# Main_v1.net
KiCad netlist of a schematic drawn in EAGLE
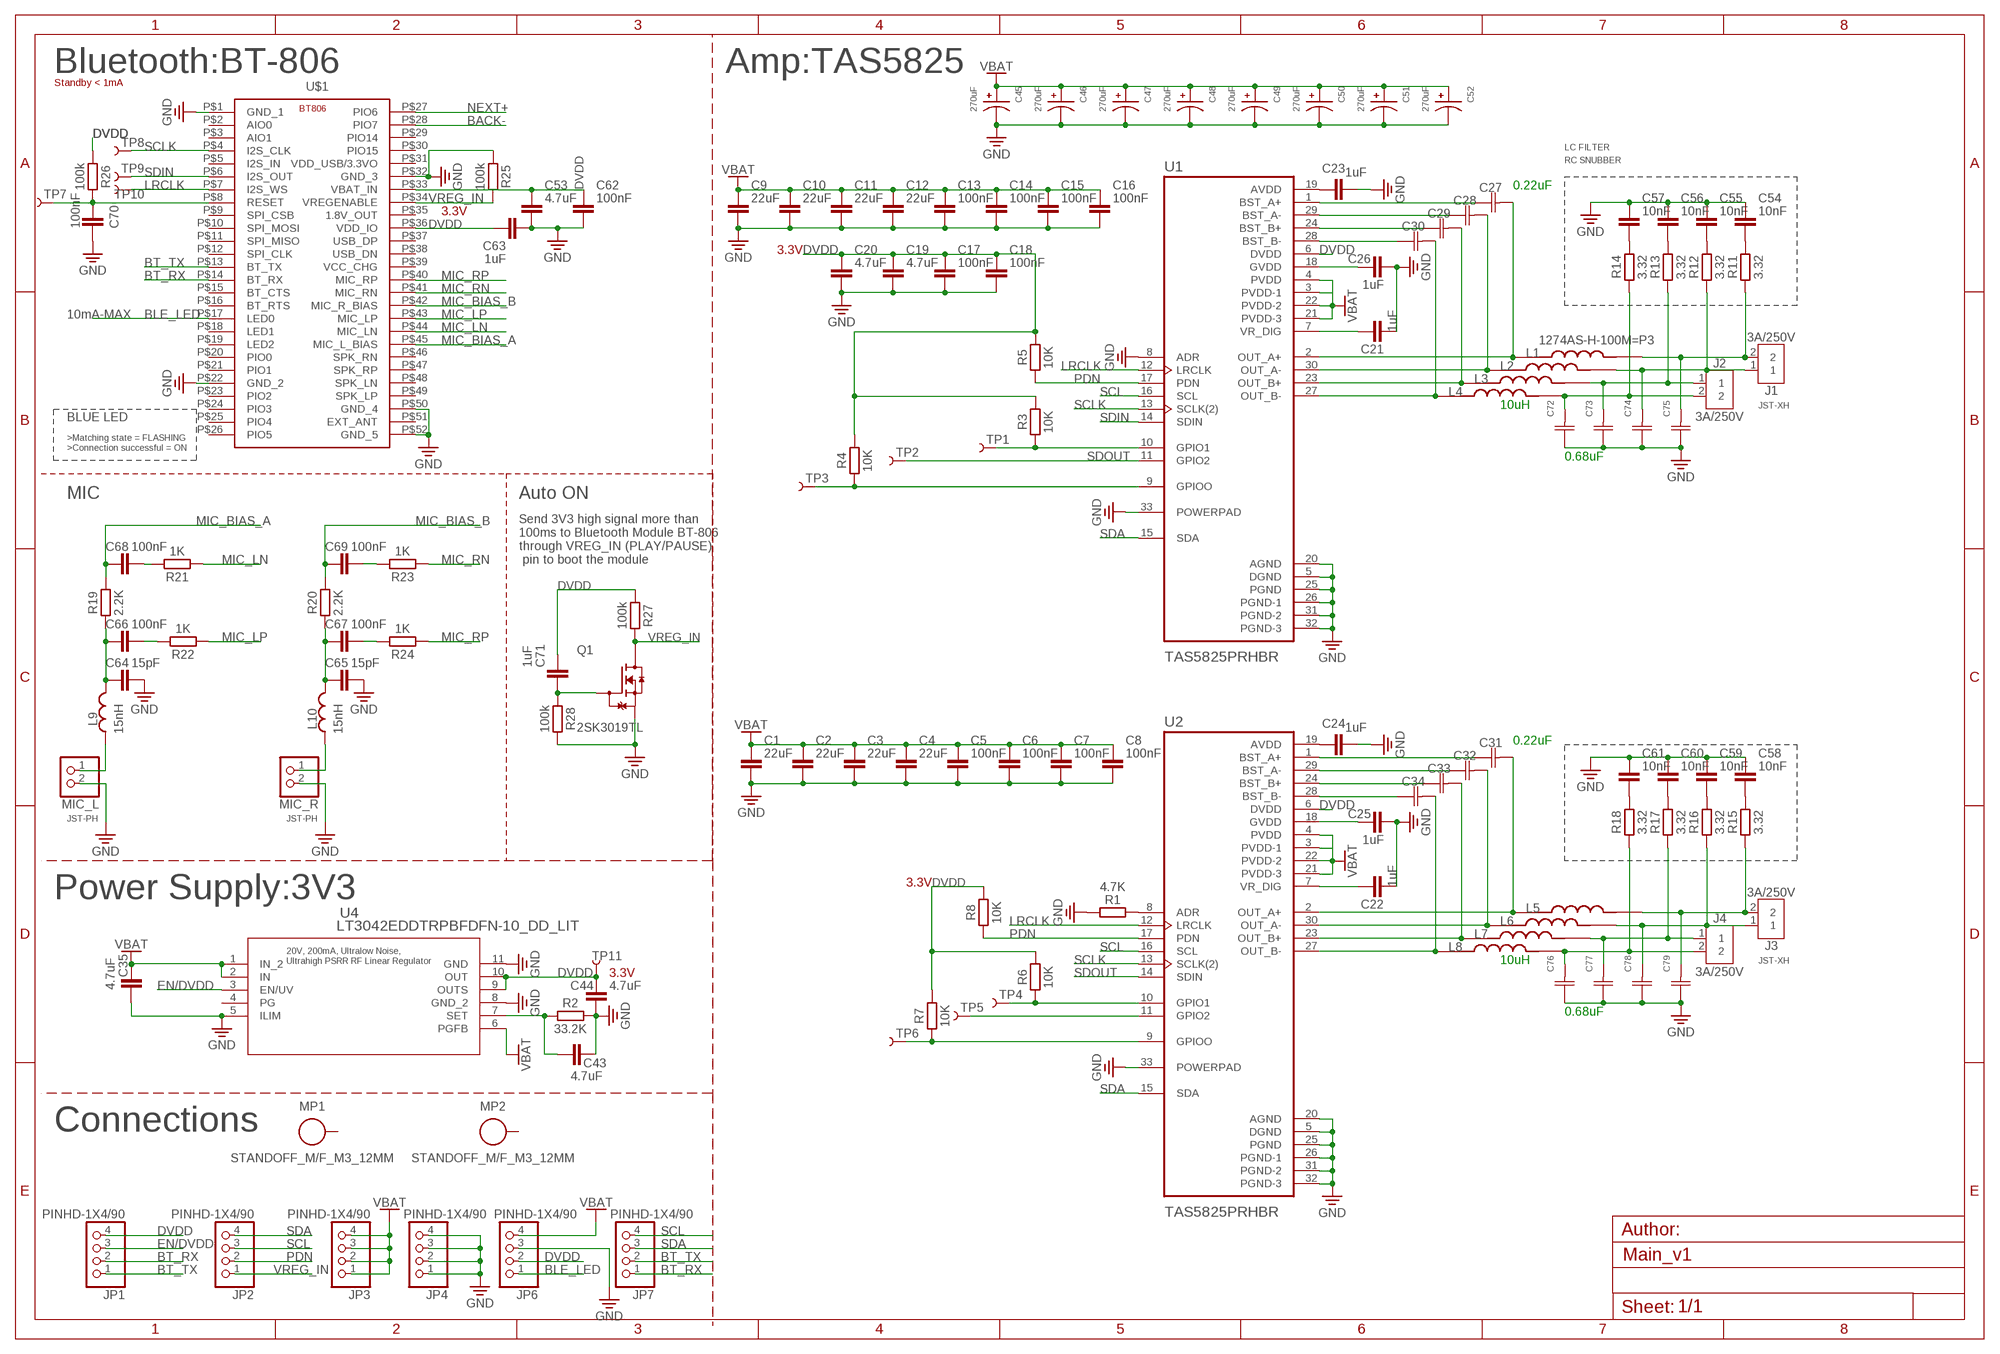
[diagram p0: schematic, sheet 1]

(export (version "E")
  (design (tool "Eeschema 10.0.6"))
  (components
    (comp (ref "C1")
      (value "22uF")
      (footprint "eagle-import:CAPC2012X110")
      (libsource (lib "eagle-import") (part "CCHIP-0805(2012-METRIC)_"))
    )
    (comp (ref "C2")
      (value "22uF")
      (footprint "eagle-import:CAPC2012X110")
      (libsource (lib "eagle-import") (part "CCHIP-0805(2012-METRIC)_"))
    )
    (comp (ref "C3")
      (value "22uF")
      (footprint "eagle-import:CAPC2012X110")
      (libsource (lib "eagle-import") (part "CCHIP-0805(2012-METRIC)_"))
    )
    (comp (ref "C4")
      (value "22uF")
      (footprint "eagle-import:CAPC2012X110")
      (libsource (lib "eagle-import") (part "CCHIP-0805(2012-METRIC)_"))
    )
    (comp (ref "C5")
      (value "100nF")
      (footprint "eagle-import:CAPC2012X110")
      (libsource (lib "eagle-import") (part "CCHIP-0805(2012-METRIC)_"))
    )
    (comp (ref "C6")
      (value "100nF")
      (footprint "eagle-import:CAPC2012X110")
      (libsource (lib "eagle-import") (part "CCHIP-0805(2012-METRIC)_"))
    )
    (comp (ref "C7")
      (value "100nF")
      (footprint "eagle-import:CAPC2012X110")
      (libsource (lib "eagle-import") (part "CCHIP-0805(2012-METRIC)_"))
    )
    (comp (ref "C8")
      (value "100nF")
      (footprint "eagle-import:CAPC2012X110")
      (libsource (lib "eagle-import") (part "CCHIP-0805(2012-METRIC)_"))
    )
    (comp (ref "C9")
      (value "22uF")
      (footprint "eagle-import:CAPC2012X110")
      (libsource (lib "eagle-import") (part "CCHIP-0805(2012-METRIC)_"))
    )
    (comp (ref "C10")
      (value "22uF")
      (footprint "eagle-import:CAPC2012X110")
      (libsource (lib "eagle-import") (part "CCHIP-0805(2012-METRIC)_"))
    )
    (comp (ref "C11")
      (value "22uF")
      (footprint "eagle-import:CAPC2012X110")
      (libsource (lib "eagle-import") (part "CCHIP-0805(2012-METRIC)_"))
    )
    (comp (ref "C12")
      (value "22uF")
      (footprint "eagle-import:CAPC2012X110")
      (libsource (lib "eagle-import") (part "CCHIP-0805(2012-METRIC)_"))
    )
    (comp (ref "C13")
      (value "100nF")
      (footprint "eagle-import:CAPC2012X110")
      (libsource (lib "eagle-import") (part "CCHIP-0805(2012-METRIC)_"))
    )
    (comp (ref "C14")
      (value "100nF")
      (footprint "eagle-import:CAPC2012X110")
      (libsource (lib "eagle-import") (part "CCHIP-0805(2012-METRIC)_"))
    )
    (comp (ref "C15")
      (value "100nF")
      (footprint "eagle-import:CAPC2012X110")
      (libsource (lib "eagle-import") (part "CCHIP-0805(2012-METRIC)_"))
    )
    (comp (ref "C16")
      (value "100nF")
      (footprint "eagle-import:CAPC2012X110")
      (libsource (lib "eagle-import") (part "CCHIP-0805(2012-METRIC)_"))
    )
    (comp (ref "C17")
      (value "100nF")
      (footprint "eagle-import:CAPC2012X110")
      (libsource (lib "eagle-import") (part "CCHIP-0805(2012-METRIC)_"))
    )
    (comp (ref "C18")
      (value "100nF")
      (footprint "eagle-import:CAPC2012X110")
      (libsource (lib "eagle-import") (part "CCHIP-0805(2012-METRIC)_"))
    )
    (comp (ref "C19")
      (value "4.7uF")
      (footprint "eagle-import:CAPC3216X135")
      (libsource (lib "eagle-import") (part "CCHIP-1206(3216-METRIC)_"))
    )
    (comp (ref "C20")
      (value "4.7uF")
      (footprint "eagle-import:CAPC3216X135")
      (libsource (lib "eagle-import") (part "CCHIP-1206(3216-METRIC)_"))
    )
    (comp (ref "C21")
      (value "1uF")
      (footprint "eagle-import:CAPC2012X110")
      (libsource (lib "eagle-import") (part "CCHIP-0805(2012-METRIC)_"))
    )
    (comp (ref "C22")
      (value "1uF")
      (footprint "eagle-import:CAPC2012X110")
      (libsource (lib "eagle-import") (part "CCHIP-0805(2012-METRIC)_"))
    )
    (comp (ref "C23")
      (value "1uF")
      (footprint "eagle-import:CAPC2012X110")
      (libsource (lib "eagle-import") (part "CCHIP-0805(2012-METRIC)_"))
    )
    (comp (ref "C24")
      (value "1uF")
      (footprint "eagle-import:CAPC2012X110")
      (libsource (lib "eagle-import") (part "CCHIP-0805(2012-METRIC)_"))
    )
    (comp (ref "C25")
      (value "1uF")
      (footprint "eagle-import:CAPC2012X110")
      (libsource (lib "eagle-import") (part "CCHIP-0805(2012-METRIC)_"))
    )
    (comp (ref "C26")
      (value "1uF")
      (footprint "eagle-import:CAPC2012X110")
      (libsource (lib "eagle-import") (part "CCHIP-0805(2012-METRIC)_"))
    )
    (comp (ref "C27")
      (value "0.22uF")
      (footprint "eagle-import:CAPM7.2X7.2_5_1_VIS")
      (fields
        (field (name "MANUFACTURER_PART_NUMBER") "PHE426HJ6220JR05")
        (field (name "COPYRIGHT") "Copyright (C) 2021 Ultra Librarian. All rights reserved.")
      )
      (libsource (lib "eagle-import") (part "PHE426HJ6220JR05CAPM7.2X7.2_5_1_VIS"))
    )
    (comp (ref "C28")
      (value "0.22uF")
      (footprint "eagle-import:CAPM7.2X7.2_5_1_VIS")
      (fields
        (field (name "MANUFACTURER_PART_NUMBER") "PHE426HJ6220JR05")
        (field (name "COPYRIGHT") "Copyright (C) 2021 Ultra Librarian. All rights reserved.")
      )
      (libsource (lib "eagle-import") (part "PHE426HJ6220JR05CAPM7.2X7.2_5_1_VIS"))
    )
    (comp (ref "C29")
      (value "0.22uF")
      (footprint "eagle-import:CAPM7.2X7.2_5_1_VIS")
      (fields
        (field (name "MANUFACTURER_PART_NUMBER") "PHE426HJ6220JR05")
        (field (name "COPYRIGHT") "Copyright (C) 2021 Ultra Librarian. All rights reserved.")
      )
      (libsource (lib "eagle-import") (part "PHE426HJ6220JR05CAPM7.2X7.2_5_1_VIS"))
    )
    (comp (ref "C30")
      (value "0.22uF")
      (footprint "eagle-import:CAPM7.2X7.2_5_1_VIS")
      (fields
        (field (name "MANUFACTURER_PART_NUMBER") "PHE426HJ6220JR05")
        (field (name "COPYRIGHT") "Copyright (C) 2021 Ultra Librarian. All rights reserved.")
      )
      (libsource (lib "eagle-import") (part "PHE426HJ6220JR05CAPM7.2X7.2_5_1_VIS"))
    )
    (comp (ref "C31")
      (value "0.22uF")
      (footprint "eagle-import:CAPM7.2X7.2_5_1_VIS")
      (fields
        (field (name "MANUFACTURER_PART_NUMBER") "PHE426HJ6220JR05")
        (field (name "COPYRIGHT") "Copyright (C) 2021 Ultra Librarian. All rights reserved.")
      )
      (libsource (lib "eagle-import") (part "PHE426HJ6220JR05CAPM7.2X7.2_5_1_VIS"))
    )
    (comp (ref "C32")
      (value "0.22uF")
      (footprint "eagle-import:CAPM7.2X7.2_5_1_VIS")
      (fields
        (field (name "MANUFACTURER_PART_NUMBER") "PHE426HJ6220JR05")
        (field (name "COPYRIGHT") "Copyright (C) 2021 Ultra Librarian. All rights reserved.")
      )
      (libsource (lib "eagle-import") (part "PHE426HJ6220JR05CAPM7.2X7.2_5_1_VIS"))
    )
    (comp (ref "C33")
      (value "0.22uF")
      (footprint "eagle-import:CAPM7.2X7.2_5_1_VIS")
      (fields
        (field (name "MANUFACTURER_PART_NUMBER") "PHE426HJ6220JR05")
        (field (name "COPYRIGHT") "Copyright (C) 2021 Ultra Librarian. All rights reserved.")
      )
      (libsource (lib "eagle-import") (part "PHE426HJ6220JR05CAPM7.2X7.2_5_1_VIS"))
    )
    (comp (ref "C34")
      (value "0.22uF")
      (footprint "eagle-import:CAPM7.2X7.2_5_1_VIS")
      (fields
        (field (name "MANUFACTURER_PART_NUMBER") "PHE426HJ6220JR05")
        (field (name "COPYRIGHT") "Copyright (C) 2021 Ultra Librarian. All rights reserved.")
      )
      (libsource (lib "eagle-import") (part "PHE426HJ6220JR05CAPM7.2X7.2_5_1_VIS"))
    )
    (comp (ref "C35")
      (value "4.7uF")
      (footprint "eagle-import:CAPC2012X110")
      (libsource (lib "eagle-import") (part "CCHIP-0805(2012-METRIC)_"))
    )
    (comp (ref "C43")
      (value "4.7uF")
      (footprint "eagle-import:CAPC2012X110")
      (libsource (lib "eagle-import") (part "CCHIP-0805(2012-METRIC)_"))
    )
    (comp (ref "C44")
      (value "4.7uF")
      (footprint "eagle-import:CAPC2012X110")
      (libsource (lib "eagle-import") (part "CCHIP-0805(2012-METRIC)_"))
    )
    (comp (ref "C45")
      (value "270uF")
      (footprint "eagle-import:CAP_16SVPG270M")
      (fields (field (name "MANUFACTURER") "Panasonic"))
      (libsource (lib "eagle-import") (part "16SVPG270M"))
    )
    (comp (ref "C46")
      (value "270uF")
      (footprint "eagle-import:CAP_16SVPG270M")
      (fields (field (name "MANUFACTURER") "Panasonic"))
      (libsource (lib "eagle-import") (part "16SVPG270M"))
    )
    (comp (ref "C47")
      (value "270uF")
      (footprint "eagle-import:CAP_16SVPG270M")
      (fields (field (name "MANUFACTURER") "Panasonic"))
      (libsource (lib "eagle-import") (part "16SVPG270M"))
    )
    (comp (ref "C48")
      (value "270uF")
      (footprint "eagle-import:CAP_16SVPG270M")
      (fields (field (name "MANUFACTURER") "Panasonic"))
      (libsource (lib "eagle-import") (part "16SVPG270M"))
    )
    (comp (ref "C49")
      (value "270uF")
      (footprint "eagle-import:CAP_16SVPG270M")
      (fields (field (name "MANUFACTURER") "Panasonic"))
      (libsource (lib "eagle-import") (part "16SVPG270M"))
    )
    (comp (ref "C50")
      (value "270uF")
      (footprint "eagle-import:CAP_16SVPG270M")
      (fields (field (name "MANUFACTURER") "Panasonic"))
      (libsource (lib "eagle-import") (part "16SVPG270M"))
    )
    (comp (ref "C51")
      (value "270uF")
      (footprint "eagle-import:CAP_16SVPG270M")
      (fields (field (name "MANUFACTURER") "Panasonic"))
      (libsource (lib "eagle-import") (part "16SVPG270M"))
    )
    (comp (ref "C52")
      (value "270uF")
      (footprint "eagle-import:CAP_16SVPG270M")
      (fields (field (name "MANUFACTURER") "Panasonic"))
      (libsource (lib "eagle-import") (part "16SVPG270M"))
    )
    (comp (ref "C53")
      (value "4.7uF")
      (footprint "eagle-import:CAPC2012X110")
      (libsource (lib "eagle-import") (part "CCHIP-0805(2012-METRIC)_"))
    )
    (comp (ref "C54")
      (value "10nF")
      (footprint "eagle-import:CAPC2012X110")
      (libsource (lib "eagle-import") (part "CCHIP-0805(2012-METRIC)_"))
    )
    (comp (ref "C55")
      (value "10nF")
      (footprint "eagle-import:CAPC2012X110")
      (libsource (lib "eagle-import") (part "CCHIP-0805(2012-METRIC)_"))
    )
    (comp (ref "C56")
      (value "10nF")
      (footprint "eagle-import:CAPC2012X110")
      (libsource (lib "eagle-import") (part "CCHIP-0805(2012-METRIC)_"))
    )
    (comp (ref "C57")
      (value "10nF")
      (footprint "eagle-import:CAPC2012X110")
      (libsource (lib "eagle-import") (part "CCHIP-0805(2012-METRIC)_"))
    )
    (comp (ref "C58")
      (value "10nF")
      (footprint "eagle-import:CAPC2012X110")
      (libsource (lib "eagle-import") (part "CCHIP-0805(2012-METRIC)_"))
    )
    (comp (ref "C59")
      (value "10nF")
      (footprint "eagle-import:CAPC2012X110")
      (libsource (lib "eagle-import") (part "CCHIP-0805(2012-METRIC)_"))
    )
    (comp (ref "C60")
      (value "10nF")
      (footprint "eagle-import:CAPC2012X110")
      (libsource (lib "eagle-import") (part "CCHIP-0805(2012-METRIC)_"))
    )
    (comp (ref "C61")
      (value "10nF")
      (footprint "eagle-import:CAPC2012X110")
      (libsource (lib "eagle-import") (part "CCHIP-0805(2012-METRIC)_"))
    )
    (comp (ref "C62")
      (value "100nF")
      (footprint "eagle-import:CAPC2012X110")
      (libsource (lib "eagle-import") (part "CCHIP-0805(2012-METRIC)_"))
    )
    (comp (ref "C63")
      (value "1uF")
      (footprint "eagle-import:CAPC2012X110")
      (libsource (lib "eagle-import") (part "CCHIP-0805(2012-METRIC)_"))
    )
    (comp (ref "C64")
      (value "15pF")
      (footprint "eagle-import:CAPC1005X60")
      (libsource (lib "eagle-import") (part "CCHIP-0402(1005-METRIC)_"))
    )
    (comp (ref "C65")
      (value "15pF")
      (footprint "eagle-import:CAPC1005X60")
      (libsource (lib "eagle-import") (part "CCHIP-0402(1005-METRIC)_"))
    )
    (comp (ref "C66")
      (value "100nF")
      (footprint "eagle-import:CAPC1005X60")
      (libsource (lib "eagle-import") (part "CCHIP-0402(1005-METRIC)_"))
    )
    (comp (ref "C67")
      (value "100nF")
      (footprint "eagle-import:CAPC1005X60")
      (libsource (lib "eagle-import") (part "CCHIP-0402(1005-METRIC)_"))
    )
    (comp (ref "C68")
      (value "100nF")
      (footprint "eagle-import:CAPC1005X60")
      (libsource (lib "eagle-import") (part "CCHIP-0402(1005-METRIC)_"))
    )
    (comp (ref "C69")
      (value "100nF")
      (footprint "eagle-import:CAPC1005X60")
      (libsource (lib "eagle-import") (part "CCHIP-0402(1005-METRIC)_"))
    )
    (comp (ref "C70")
      (value "100nF")
      (footprint "eagle-import:CAPC1005X60")
      (libsource (lib "eagle-import") (part "CCHIP-0402(1005-METRIC)_"))
    )
    (comp (ref "C71")
      (value "1uF")
      (footprint "eagle-import:CAPC2012X110")
      (libsource (lib "eagle-import") (part "CCHIP-0805(2012-METRIC)_"))
    )
    (comp (ref "C72")
      (value "MMK5684J63J03L16.5TR18CAPM7.2X4.5_5_VIS")
      (footprint "eagle-import:CAPM7.2X4.5_5_VIS")
      (fields
        (field (name "MANUFACTURER_PART_NUMBER") "MMK5684J63J03L16.5TR18")
        (field (name "COPYRIGHT") "Copyright (C) 2022 Ultra Librarian. All rights reserved.")
      )
      (libsource (lib "eagle-import") (part "MMK5684J63J03L16.5TR18CAPM7.2X4.5_5_VIS"))
    )
    (comp (ref "C73")
      (value "MMK5684J63J03L16.5TR18CAPM7.2X4.5_5_VIS")
      (footprint "eagle-import:CAPM7.2X4.5_5_VIS")
      (fields
        (field (name "MANUFACTURER_PART_NUMBER") "MMK5684J63J03L16.5TR18")
        (field (name "COPYRIGHT") "Copyright (C) 2022 Ultra Librarian. All rights reserved.")
      )
      (libsource (lib "eagle-import") (part "MMK5684J63J03L16.5TR18CAPM7.2X4.5_5_VIS"))
    )
    (comp (ref "C74")
      (value "MMK5684J63J03L16.5TR18CAPM7.2X4.5_5_VIS")
      (footprint "eagle-import:CAPM7.2X4.5_5_VIS")
      (fields
        (field (name "MANUFACTURER_PART_NUMBER") "MMK5684J63J03L16.5TR18")
        (field (name "COPYRIGHT") "Copyright (C) 2022 Ultra Librarian. All rights reserved.")
      )
      (libsource (lib "eagle-import") (part "MMK5684J63J03L16.5TR18CAPM7.2X4.5_5_VIS"))
    )
    (comp (ref "C75")
      (value "MMK5684J63J03L16.5TR18CAPM7.2X4.5_5_VIS")
      (footprint "eagle-import:CAPM7.2X4.5_5_VIS")
      (fields
        (field (name "MANUFACTURER_PART_NUMBER") "MMK5684J63J03L16.5TR18")
        (field (name "COPYRIGHT") "Copyright (C) 2022 Ultra Librarian. All rights reserved.")
      )
      (libsource (lib "eagle-import") (part "MMK5684J63J03L16.5TR18CAPM7.2X4.5_5_VIS"))
    )
    (comp (ref "C76")
      (value "MMK5684J63J03L16.5TR18CAPM7.2X4.5_5_VIS")
      (footprint "eagle-import:CAPM7.2X4.5_5_VIS")
      (fields
        (field (name "MANUFACTURER_PART_NUMBER") "MMK5684J63J03L16.5TR18")
        (field (name "COPYRIGHT") "Copyright (C) 2022 Ultra Librarian. All rights reserved.")
      )
      (libsource (lib "eagle-import") (part "MMK5684J63J03L16.5TR18CAPM7.2X4.5_5_VIS"))
    )
    (comp (ref "C77")
      (value "MMK5684J63J03L16.5TR18CAPM7.2X4.5_5_VIS")
      (footprint "eagle-import:CAPM7.2X4.5_5_VIS")
      (fields
        (field (name "MANUFACTURER_PART_NUMBER") "MMK5684J63J03L16.5TR18")
        (field (name "COPYRIGHT") "Copyright (C) 2022 Ultra Librarian. All rights reserved.")
      )
      (libsource (lib "eagle-import") (part "MMK5684J63J03L16.5TR18CAPM7.2X4.5_5_VIS"))
    )
    (comp (ref "C78")
      (value "MMK5684J63J03L16.5TR18CAPM7.2X4.5_5_VIS")
      (footprint "eagle-import:CAPM7.2X4.5_5_VIS")
      (fields
        (field (name "MANUFACTURER_PART_NUMBER") "MMK5684J63J03L16.5TR18")
        (field (name "COPYRIGHT") "Copyright (C) 2022 Ultra Librarian. All rights reserved.")
      )
      (libsource (lib "eagle-import") (part "MMK5684J63J03L16.5TR18CAPM7.2X4.5_5_VIS"))
    )
    (comp (ref "C79")
      (value "MMK5684J63J03L16.5TR18CAPM7.2X4.5_5_VIS")
      (footprint "eagle-import:CAPM7.2X4.5_5_VIS")
      (fields
        (field (name "MANUFACTURER_PART_NUMBER") "MMK5684J63J03L16.5TR18")
        (field (name "COPYRIGHT") "Copyright (C) 2022 Ultra Librarian. All rights reserved.")
      )
      (libsource (lib "eagle-import") (part "MMK5684J63J03L16.5TR18CAPM7.2X4.5_5_VIS"))
    )
    (comp (ref "J1")
      (value "3A/250V")
      (footprint "eagle-import:B2B-XH-A")
      (fields (field (name "MANUFACTURER") "JST (XH CONNECTOR)") (field (name "MPN") "B2B-XH-A"))
      (libsource (lib "eagle-import") (part "B2B-XH-A"))
    )
    (comp (ref "J2")
      (value "3A/250V")
      (footprint "eagle-import:B2B-XH-A")
      (fields (field (name "MANUFACTURER") "JST (XH CONNECTOR)") (field (name "MPN") "B2B-XH-A"))
      (libsource (lib "eagle-import") (part "B2B-XH-A"))
    )
    (comp (ref "J3")
      (value "3A/250V")
      (footprint "eagle-import:B2B-XH-A")
      (fields (field (name "MANUFACTURER") "JST (XH CONNECTOR)") (field (name "MPN") "B2B-XH-A"))
      (libsource (lib "eagle-import") (part "B2B-XH-A"))
    )
    (comp (ref "J4")
      (value "3A/250V")
      (footprint "eagle-import:B2B-XH-A")
      (fields (field (name "MANUFACTURER") "JST (XH CONNECTOR)") (field (name "MPN") "B2B-XH-A"))
      (libsource (lib "eagle-import") (part "B2B-XH-A"))
    )
    (comp (ref "JP1")
      (value "PINHD-1X4/90")
      (footprint "eagle-import:1X04_90")
      (libsource (lib "eagle-import") (part "PINHD-1X4/90"))
    )
    (comp (ref "JP2")
      (value "PINHD-1X4/90")
      (footprint "eagle-import:1X04_90")
      (libsource (lib "eagle-import") (part "PINHD-1X4/90"))
    )
    (comp (ref "JP3")
      (value "PINHD-1X4/90")
      (footprint "eagle-import:1X04_90")
      (libsource (lib "eagle-import") (part "PINHD-1X4/90"))
    )
    (comp (ref "JP4")
      (value "PINHD-1X4/90")
      (footprint "eagle-import:1X04_90")
      (libsource (lib "eagle-import") (part "PINHD-1X4/90"))
    )
    (comp (ref "JP6")
      (value "PINHD-1X4/90")
      (footprint "eagle-import:1X04_90")
      (libsource (lib "eagle-import") (part "PINHD-1X4/90"))
    )
    (comp (ref "JP7")
      (value "PINHD-1X4/90")
      (footprint "eagle-import:1X04_90")
      (libsource (lib "eagle-import") (part "PINHD-1X4/90"))
    )
    (comp (ref "L1")
      (value "1274AS-H-100M=P3")
      (footprint "eagle-import:IND_1274AS-H-100M=P3")
      (fields (field (name "MANUFACTURER") "Murata"))
      (libsource (lib "eagle-import") (part "1274AS-H-100M=P3"))
    )
    (comp (ref "L2")
      (value "1274AS-H-100M=P3")
      (footprint "eagle-import:IND_1274AS-H-100M=P3")
      (fields (field (name "MANUFACTURER") "Murata"))
      (libsource (lib "eagle-import") (part "1274AS-H-100M=P3"))
    )
    (comp (ref "L3")
      (value "1274AS-H-100M=P3")
      (footprint "eagle-import:IND_1274AS-H-100M=P3")
      (fields (field (name "MANUFACTURER") "Murata"))
      (libsource (lib "eagle-import") (part "1274AS-H-100M=P3"))
    )
    (comp (ref "L4")
      (value "1274AS-H-100M=P3")
      (footprint "eagle-import:IND_1274AS-H-100M=P3")
      (fields (field (name "MANUFACTURER") "Murata"))
      (libsource (lib "eagle-import") (part "1274AS-H-100M=P3"))
    )
    (comp (ref "L5")
      (value "1274AS-H-100M=P3")
      (footprint "eagle-import:IND_1274AS-H-100M=P3")
      (fields (field (name "MANUFACTURER") "Murata"))
      (libsource (lib "eagle-import") (part "1274AS-H-100M=P3"))
    )
    (comp (ref "L6")
      (value "1274AS-H-100M=P3")
      (footprint "eagle-import:IND_1274AS-H-100M=P3")
      (fields (field (name "MANUFACTURER") "Murata"))
      (libsource (lib "eagle-import") (part "1274AS-H-100M=P3"))
    )
    (comp (ref "L7")
      (value "1274AS-H-100M=P3")
      (footprint "eagle-import:IND_1274AS-H-100M=P3")
      (fields (field (name "MANUFACTURER") "Murata"))
      (libsource (lib "eagle-import") (part "1274AS-H-100M=P3"))
    )
    (comp (ref "L8")
      (value "1274AS-H-100M=P3")
      (footprint "eagle-import:IND_1274AS-H-100M=P3")
      (fields (field (name "MANUFACTURER") "Murata"))
      (libsource (lib "eagle-import") (part "1274AS-H-100M=P3"))
    )
    (comp (ref "L9")
      (value "15nH")
      (footprint "eagle-import:INDC1006X60N")
      (libsource (lib "eagle-import") (part "LCHIP-0402(1006-METRIC)_"))
    )
    (comp (ref "L10")
      (value "15nH")
      (footprint "eagle-import:INDC1006X60N")
      (libsource (lib "eagle-import") (part "LCHIP-0402(1006-METRIC)_"))
    )
    (comp (ref "MIC_L")
      (value "JST_2PIN-THM")
      (footprint "eagle-import:JST-PH-2-THM")
      (libsource (lib "eagle-import") (part "JST_2PIN-THM"))
    )
    (comp (ref "MIC_R")
      (value "JST_2PIN-THM")
      (footprint "eagle-import:JST-PH-2-THM")
      (libsource (lib "eagle-import") (part "JST_2PIN-THM"))
    )
    (comp (ref "MP1")
      (value "STANDOFF_M/F_M3_12MM")
      (footprint "eagle-import:STANDOFF_HEX_MALE-FEMALE_550X1200_M3X0.5_MTGP850H320")
      (libsource (lib "eagle-import") (part "STANDOFF_M/FM3_12MM_"))
    )
    (comp (ref "MP2")
      (value "STANDOFF_M/F_M3_12MM")
      (footprint "eagle-import:STANDOFF_HEX_MALE-FEMALE_550X1200_M3X0.5_MTGP850H320")
      (libsource (lib "eagle-import") (part "STANDOFF_M/FM3_12MM_"))
    )
    (comp (ref "Q1")
      (value "2SK3019TL")
      (footprint "eagle-import:TRANS_2SK3019TL")
      (fields (field (name "MANUFACTURER") "ROHM"))
      (libsource (lib "eagle-import") (part "2SK3019TL"))
    )
    (comp (ref "R1")
      (value "4.7K")
      (footprint "eagle-import:RESC1005X40")
      (libsource (lib "eagle-import") (part "RCHIP-0402(1005-METRIC)_"))
    )
    (comp (ref "R2")
      (value "33.2K")
      (footprint "eagle-import:RESC1005X40")
      (libsource (lib "eagle-import") (part "RCHIP-0402(1005-METRIC)_"))
    )
    (comp (ref "R3")
      (value "10K")
      (footprint "eagle-import:RESC1005X40")
      (libsource (lib "eagle-import") (part "RCHIP-0402(1005-METRIC)_"))
    )
    (comp (ref "R4")
      (value "10K")
      (footprint "eagle-import:RESC1005X40")
      (libsource (lib "eagle-import") (part "RCHIP-0402(1005-METRIC)_"))
    )
    (comp (ref "R5")
      (value "10K")
      (footprint "eagle-import:RESC1005X40")
      (libsource (lib "eagle-import") (part "RCHIP-0402(1005-METRIC)_"))
    )
    (comp (ref "R6")
      (value "10K")
      (footprint "eagle-import:RESC1005X40")
      (libsource (lib "eagle-import") (part "RCHIP-0402(1005-METRIC)_"))
    )
    (comp (ref "R7")
      (value "10K")
      (footprint "eagle-import:RESC1005X40")
      (libsource (lib "eagle-import") (part "RCHIP-0402(1005-METRIC)_"))
    )
    (comp (ref "R8")
      (value "10K")
      (footprint "eagle-import:RESC1005X40")
      (libsource (lib "eagle-import") (part "RCHIP-0402(1005-METRIC)_"))
    )
    (comp (ref "R11")
      (value "3.32")
      (footprint "eagle-import:RESC1005X40")
      (libsource (lib "eagle-import") (part "RCHIP-0402(1005-METRIC)_"))
    )
    (comp (ref "R12")
      (value "3.32")
      (footprint "eagle-import:RESC1005X40")
      (libsource (lib "eagle-import") (part "RCHIP-0402(1005-METRIC)_"))
    )
    (comp (ref "R13")
      (value "3.32")
      (footprint "eagle-import:RESC1005X40")
      (libsource (lib "eagle-import") (part "RCHIP-0402(1005-METRIC)_"))
    )
    (comp (ref "R14")
      (value "3.32")
      (footprint "eagle-import:RESC1005X40")
      (libsource (lib "eagle-import") (part "RCHIP-0402(1005-METRIC)_"))
    )
    (comp (ref "R15")
      (value "3.32")
      (footprint "eagle-import:RESC1005X40")
      (libsource (lib "eagle-import") (part "RCHIP-0402(1005-METRIC)_"))
    )
    (comp (ref "R16")
      (value "3.32")
      (footprint "eagle-import:RESC1005X40")
      (libsource (lib "eagle-import") (part "RCHIP-0402(1005-METRIC)_"))
    )
    (comp (ref "R17")
      (value "3.32")
      (footprint "eagle-import:RESC1005X40")
      (libsource (lib "eagle-import") (part "RCHIP-0402(1005-METRIC)_"))
    )
    (comp (ref "R18")
      (value "3.32")
      (footprint "eagle-import:RESC1005X40")
      (libsource (lib "eagle-import") (part "RCHIP-0402(1005-METRIC)_"))
    )
    (comp (ref "R19")
      (value "2.2K")
      (footprint "eagle-import:RESC1005X40")
      (libsource (lib "eagle-import") (part "RCHIP-0402(1005-METRIC)_"))
    )
    (comp (ref "R20")
      (value "2.2K")
      (footprint "eagle-import:RESC1005X40")
      (libsource (lib "eagle-import") (part "RCHIP-0402(1005-METRIC)_"))
    )
    (comp (ref "R21")
      (value "1K")
      (footprint "eagle-import:RESC1005X40")
      (libsource (lib "eagle-import") (part "RCHIP-0402(1005-METRIC)_"))
    )
    (comp (ref "R22")
      (value "1K")
      (footprint "eagle-import:RESC1005X40")
      (libsource (lib "eagle-import") (part "RCHIP-0402(1005-METRIC)_"))
    )
    (comp (ref "R23")
      (value "1K")
      (footprint "eagle-import:RESC1005X40")
      (libsource (lib "eagle-import") (part "RCHIP-0402(1005-METRIC)_"))
    )
    (comp (ref "R24")
      (value "1K")
      (footprint "eagle-import:RESC1005X40")
      (libsource (lib "eagle-import") (part "RCHIP-0402(1005-METRIC)_"))
    )
    (comp (ref "R25")
      (value "100k")
      (footprint "eagle-import:RESC1005X40")
      (libsource (lib "eagle-import") (part "RCHIP-0402(1005-METRIC)_"))
    )
    (comp (ref "R26")
      (value "100k")
      (footprint "eagle-import:RESC1005X40")
      (libsource (lib "eagle-import") (part "RCHIP-0402(1005-METRIC)_"))
    )
    (comp (ref "R27")
      (value "100k")
      (footprint "eagle-import:RESC1005X40")
      (libsource (lib "eagle-import") (part "RCHIP-0402(1005-METRIC)_"))
    )
    (comp (ref "R28")
      (value "100k")
      (footprint "eagle-import:RESC1005X40")
      (libsource (lib "eagle-import") (part "RCHIP-0402(1005-METRIC)_"))
    )
    (comp (ref "TP1")
      (value "TEST-POINT3")
      (footprint "eagle-import:PAD.03X.03")
      (libsource (lib "eagle-import") (part "TEST-POINT3"))
    )
    (comp (ref "TP2")
      (value "TEST-POINT3")
      (footprint "eagle-import:PAD.03X.03")
      (libsource (lib "eagle-import") (part "TEST-POINT3"))
    )
    (comp (ref "TP3")
      (value "TEST-POINT3")
      (footprint "eagle-import:PAD.03X.03")
      (libsource (lib "eagle-import") (part "TEST-POINT3"))
    )
    (comp (ref "TP4")
      (value "TEST-POINT3")
      (footprint "eagle-import:PAD.03X.03")
      (libsource (lib "eagle-import") (part "TEST-POINT3"))
    )
    (comp (ref "TP5")
      (value "TEST-POINT3")
      (footprint "eagle-import:PAD.03X.03")
      (libsource (lib "eagle-import") (part "TEST-POINT3"))
    )
    (comp (ref "TP6")
      (value "TEST-POINT3")
      (footprint "eagle-import:PAD.03X.03")
      (libsource (lib "eagle-import") (part "TEST-POINT3"))
    )
    (comp (ref "TP7")
      (value "TEST-POINT3")
      (footprint "eagle-import:PAD.03X.03")
      (libsource (lib "eagle-import") (part "TEST-POINT3"))
    )
    (comp (ref "TP8")
      (value "TEST-POINT3X5")
      (footprint "eagle-import:PAD.03X.05")
      (libsource (lib "eagle-import") (part "TEST-POINT3X5"))
    )
    (comp (ref "TP9")
      (value "TEST-POINT3X5")
      (footprint "eagle-import:PAD.03X.05")
      (libsource (lib "eagle-import") (part "TEST-POINT3X5"))
    )
    (comp (ref "TP10")
      (value "TEST-POINT3X5")
      (footprint "eagle-import:PAD.03X.05")
      (libsource (lib "eagle-import") (part "TEST-POINT3X5"))
    )
    (comp (ref "TP11")
      (value "TEST-POINT3X5")
      (footprint "eagle-import:PAD.03X.05")
      (libsource (lib "eagle-import") (part "TEST-POINT3X5"))
    )
    (comp (ref "U$1")
      (value "BT806")
      (footprint "eagle-import:BT806")
      (libsource (lib "eagle-import") (part "BT806"))
    )
    (comp (ref "U1")
      (value "TAS5825PRHBR")
      (footprint "eagle-import:IC_ADS125H01IRHBT")
      (libsource (lib "eagle-import") (part "TAS5825PRHBR"))
    )
    (comp (ref "U2")
      (value "TAS5825PRHBR")
      (footprint "eagle-import:IC_ADS125H01IRHBT")
      (libsource (lib "eagle-import") (part "TAS5825PRHBR"))
    )
    (comp (ref "U4")
      (value "LT3042EDDTRPBFDFN-10_DD_LIT")
      (footprint "eagle-import:DFN-10_DD_LIT")
      (fields
        (field (name "MANUFACTURER_PART_NUMBER") "LT3042EDD#TRPBF")
        (field (name "COPYRIGHT") "Copyright (C) 2021 Ultra Librarian. All rights reserved.")
      )
      (libsource (lib "eagle-import") (part "LT3042EDDTRPBFDFN-10_DD_LIT"))
    )
  )
  (nets
    (net (code "1") (name "/BACK-") (class "Default")
      (node (ref "U$1") (pin "P$28") (pinfunction "PIO7_P$28") (pintype "bidirectional"))
    )
    (net (code "2") (name "/BLE_LED") (class "Default")
      (node (ref "JP6") (pin "1") (pinfunction "1_1") (pintype "passive"))
      (node (ref "U$1") (pin "P$17") (pinfunction "LED0_P$17") (pintype "bidirectional"))
    )
    (net (code "3") (name "/BT_RX") (class "Default")
      (node (ref "JP1") (pin "2") (pinfunction "2_2") (pintype "passive"))
      (node (ref "JP7") (pin "1") (pinfunction "1_1") (pintype "passive"))
      (node (ref "U$1") (pin "P$14") (pinfunction "BT_RX_P$14") (pintype "bidirectional"))
    )
    (net (code "4") (name "/BT_TX") (class "Default")
      (node (ref "JP1") (pin "1") (pinfunction "1_1") (pintype "passive"))
      (node (ref "JP7") (pin "2") (pinfunction "2_2") (pintype "passive"))
      (node (ref "U$1") (pin "P$13") (pinfunction "BT_TX_P$13") (pintype "bidirectional"))
    )
    (net (code "5") (name "/DVDD") (class "Default")
      (node (ref "C17") (pin "1") (pinfunction "1_1") (pintype "passive"))
      (node (ref "C18") (pin "1") (pinfunction "1_1") (pintype "passive"))
      (node (ref "C19") (pin "1") (pinfunction "1_1") (pintype "passive"))
      (node (ref "C20") (pin "1") (pinfunction "1_1") (pintype "passive"))
      (node (ref "C44") (pin "2") (pinfunction "2_2") (pintype "passive"))
      (node (ref "C53") (pin "1") (pinfunction "1_1") (pintype "passive"))
      (node (ref "C62") (pin "1") (pinfunction "1_1") (pintype "passive"))
      (node (ref "C63") (pin "1") (pinfunction "1_1") (pintype "passive"))
      (node (ref "C71") (pin "1") (pinfunction "1_1") (pintype "passive"))
      (node (ref "JP1") (pin "4") (pinfunction "4_4") (pintype "passive"))
      (node (ref "JP6") (pin "2") (pinfunction "2_2") (pintype "passive"))
      (node (ref "R26") (pin "1") (pinfunction "1_1") (pintype "passive"))
      (node (ref "R27") (pin "1") (pinfunction "1_1") (pintype "passive"))
      (node (ref "R3") (pin "2") (pinfunction "2_2") (pintype "passive"))
      (node (ref "R4") (pin "2") (pinfunction "2_2") (pintype "passive"))
      (node (ref "R5") (pin "2") (pinfunction "2_2") (pintype "passive"))
      (node (ref "R6") (pin "2") (pinfunction "2_2") (pintype "passive"))
      (node (ref "R7") (pin "2") (pinfunction "2_2") (pintype "passive"))
      (node (ref "R8") (pin "2") (pinfunction "2_2") (pintype "passive"))
      (node (ref "TP11") (pin "P$1") (pinfunction "1_P$1") (pintype "bidirectional"))
      (node (ref "U$1") (pin "P$33") (pinfunction "VBAT_IN_P$33") (pintype "bidirectional"))
      (node (ref "U$1") (pin "P$36") (pinfunction "VDD_IO_P$36") (pintype "bidirectional"))
      (node (ref "U1") (pin "6") (pinfunction "DVDD_6") (pintype "power_in"))
      (node (ref "U2") (pin "6") (pinfunction "DVDD_6") (pintype "power_in"))
      (node (ref "U4") (pin "10") (pinfunction "OUT_10") (pintype "output"))
      (node (ref "U4") (pin "9") (pinfunction "OUTS_9") (pintype "output"))
    )
    (net (code "6") (name "/EN{slash}DVDD") (class "Default")
      (node (ref "JP1") (pin "3") (pinfunction "3_3") (pintype "passive"))
      (node (ref "U4") (pin "3") (pinfunction "EN/UV_3") (pintype "output"))
    )
    (net (code "7") (name "/LRCLK") (class "Default")
      (node (ref "TP10") (pin "P$1") (pinfunction "1_P$1") (pintype "bidirectional"))
      (node (ref "U$1") (pin "P$7") (pinfunction "I2S_WS_P$7") (pintype "bidirectional"))
      (node (ref "U1") (pin "12") (pinfunction "LRCLK_12") (pintype "input"))
      (node (ref "U2") (pin "12") (pinfunction "LRCLK_12") (pintype "input"))
    )
    (net (code "8") (name "/MIC_BIAS_A") (class "Default")
      (node (ref "C68") (pin "1") (pinfunction "1_1") (pintype "passive"))
      (node (ref "R19") (pin "2") (pinfunction "2_2") (pintype "passive"))
      (node (ref "U$1") (pin "P$45") (pinfunction "MIC_L_BIAS_P$45") (pintype "bidirectional"))
    )
    (net (code "9") (name "/MIC_BIAS_B") (class "Default")
      (node (ref "C69") (pin "1") (pinfunction "1_1") (pintype "passive"))
      (node (ref "R20") (pin "2") (pinfunction "2_2") (pintype "passive"))
      (node (ref "U$1") (pin "P$42") (pinfunction "MIC_R_BIAS_P$42") (pintype "bidirectional"))
    )
    (net (code "10") (name "/MIC_LN") (class "Default")
      (node (ref "R21") (pin "1") (pinfunction "1_1") (pintype "passive"))
      (node (ref "U$1") (pin "P$44") (pinfunction "MIC_LN_P$44") (pintype "bidirectional"))
    )
    (net (code "11") (name "/MIC_LP") (class "Default")
      (node (ref "R22") (pin "1") (pinfunction "1_1") (pintype "passive"))
      (node (ref "U$1") (pin "P$43") (pinfunction "MIC_LP_P$43") (pintype "bidirectional"))
    )
    (net (code "12") (name "/MIC_RN") (class "Default")
      (node (ref "R23") (pin "1") (pinfunction "1_1") (pintype "passive"))
      (node (ref "U$1") (pin "P$41") (pinfunction "MIC_RN_P$41") (pintype "bidirectional"))
    )
    (net (code "13") (name "/MIC_RP") (class "Default")
      (node (ref "R24") (pin "1") (pinfunction "1_1") (pintype "passive"))
      (node (ref "U$1") (pin "P$40") (pinfunction "MIC_RP_P$40") (pintype "bidirectional"))
    )
    (net (code "14") (name "/NEXT+") (class "Default")
      (node (ref "U$1") (pin "P$27") (pinfunction "PIO6_P$27") (pintype "bidirectional"))
    )
    (net (code "15") (name "/PDN") (class "Default")
      (node (ref "JP2") (pin "2") (pinfunction "2_2") (pintype "passive"))
      (node (ref "R5") (pin "1") (pinfunction "1_1") (pintype "passive"))
      (node (ref "R8") (pin "1") (pinfunction "1_1") (pintype "passive"))
      (node (ref "U1") (pin "17") (pinfunction "PDN_17") (pintype "input"))
      (node (ref "U2") (pin "17") (pinfunction "PDN_17") (pintype "input"))
    )
    (net (code "16") (name "/PG") (class "Default")
      (node (ref "U4") (pin "4") (pinfunction "PG_4") (pintype "power_in"))
    )
    (net (code "17") (name "/SCL") (class "Default")
      (node (ref "JP2") (pin "3") (pinfunction "3_3") (pintype "passive"))
      (node (ref "JP7") (pin "4") (pinfunction "4_4") (pintype "passive"))
      (node (ref "U1") (pin "16") (pinfunction "SCL_16") (pintype "input"))
      (node (ref "U2") (pin "16") (pinfunction "SCL_16") (pintype "input"))
    )
    (net (code "18") (name "/SCLK") (class "Default")
      (node (ref "TP8") (pin "P$1") (pinfunction "1_P$1") (pintype "bidirectional"))
      (node (ref "U$1") (pin "P$4") (pinfunction "I2S_CLK_P$4") (pintype "bidirectional"))
      (node (ref "U1") (pin "13") (pinfunction "SCLK(2)_13") (pintype "input"))
      (node (ref "U2") (pin "13") (pinfunction "SCLK(2)_13") (pintype "input"))
    )
    (net (code "19") (name "/SDA") (class "Default")
      (node (ref "JP2") (pin "4") (pinfunction "4_4") (pintype "passive"))
      (node (ref "JP7") (pin "3") (pinfunction "3_3") (pintype "passive"))
      (node (ref "U1") (pin "15") (pinfunction "SDA_15") (pintype "bidirectional"))
      (node (ref "U2") (pin "15") (pinfunction "SDA_15") (pintype "bidirectional"))
    )
    (net (code "20") (name "/SDIN") (class "Default")
      (node (ref "TP9") (pin "P$1") (pinfunction "1_P$1") (pintype "bidirectional"))
      (node (ref "U$1") (pin "P$6") (pinfunction "I2S_OUT_P$6") (pintype "bidirectional"))
      (node (ref "U1") (pin "14") (pinfunction "SDIN_14") (pintype "input"))
    )
    (net (code "21") (name "/SDOUT") (class "Default")
      (node (ref "TP2") (pin "P$1") (pinfunction "1_P$1") (pintype "bidirectional"))
      (node (ref "U1") (pin "11") (pinfunction "GPIO2_11") (pintype "bidirectional"))
      (node (ref "U2") (pin "14") (pinfunction "SDIN_14") (pintype "input"))
    )
    (net (code "22") (name "/VREG_IN") (class "Default")
      (node (ref "JP2") (pin "1") (pinfunction "1_1") (pintype "passive"))
      (node (ref "Q1") (pin "3") (pinfunction "D_3") (pintype "passive"))
      (node (ref "R25") (pin "2") (pinfunction "2_2") (pintype "passive"))
      (node (ref "R27") (pin "2") (pinfunction "2_2") (pintype "passive"))
      (node (ref "U$1") (pin "P$34") (pinfunction "VREGENABLE_P$34") (pintype "bidirectional"))
    )
    (net (code "23") (name "GND") (class "Default")
      (node (ref "C1") (pin "2") (pinfunction "2_2") (pintype "passive"))
      (node (ref "C10") (pin "2") (pinfunction "2_2") (pintype "passive"))
      (node (ref "C11") (pin "2") (pinfunction "2_2") (pintype "passive"))
      (node (ref "C12") (pin "2") (pinfunction "2_2") (pintype "passive"))
      (node (ref "C13") (pin "2") (pinfunction "2_2") (pintype "passive"))
      (node (ref "C14") (pin "2") (pinfunction "2_2") (pintype "passive"))
      (node (ref "C15") (pin "2") (pinfunction "2_2") (pintype "passive"))
      (node (ref "C16") (pin "2") (pinfunction "2_2") (pintype "passive"))
      (node (ref "C17") (pin "2") (pinfunction "2_2") (pintype "passive"))
      (node (ref "C18") (pin "2") (pinfunction "2_2") (pintype "passive"))
      (node (ref "C19") (pin "2") (pinfunction "2_2") (pintype "passive"))
      (node (ref "C2") (pin "2") (pinfunction "2_2") (pintype "passive"))
      (node (ref "C20") (pin "2") (pinfunction "2_2") (pintype "passive"))
      (node (ref "C21") (pin "2") (pinfunction "2_2") (pintype "passive"))
      (node (ref "C22") (pin "2") (pinfunction "2_2") (pintype "passive"))
      (node (ref "C23") (pin "2") (pinfunction "2_2") (pintype "passive"))
      (node (ref "C24") (pin "2") (pinfunction "2_2") (pintype "passive"))
      (node (ref "C25") (pin "2") (pinfunction "2_2") (pintype "passive"))
      (node (ref "C26") (pin "2") (pinfunction "2_2") (pintype "passive"))
      (node (ref "C3") (pin "2") (pinfunction "2_2") (pintype "passive"))
      (node (ref "C35") (pin "1") (pinfunction "1_1") (pintype "passive"))
      (node (ref "C4") (pin "2") (pinfunction "2_2") (pintype "passive"))
      (node (ref "C43") (pin "2") (pinfunction "2_2") (pintype "passive"))
      (node (ref "C44") (pin "1") (pinfunction "1_1") (pintype "passive"))
      (node (ref "C45") (pin "2") (pinfunction "2_2") (pintype "passive"))
      (node (ref "C46") (pin "2") (pinfunction "2_2") (pintype "passive"))
      (node (ref "C47") (pin "2") (pinfunction "2_2") (pintype "passive"))
      (node (ref "C48") (pin "2") (pinfunction "2_2") (pintype "passive"))
      (node (ref "C49") (pin "2") (pinfunction "2_2") (pintype "passive"))
      (node (ref "C5") (pin "2") (pinfunction "2_2") (pintype "passive"))
      (node (ref "C50") (pin "2") (pinfunction "2_2") (pintype "passive"))
      (node (ref "C51") (pin "2") (pinfunction "2_2") (pintype "passive"))
      (node (ref "C52") (pin "2") (pinfunction "2_2") (pintype "passive"))
      (node (ref "C53") (pin "2") (pinfunction "2_2") (pintype "passive"))
      (node (ref "C54") (pin "1") (pinfunction "1_1") (pintype "passive"))
      (node (ref "C55") (pin "1") (pinfunction "1_1") (pintype "passive"))
      (node (ref "C56") (pin "1") (pinfunction "1_1") (pintype "passive"))
      (node (ref "C57") (pin "1") (pinfunction "1_1") (pintype "passive"))
      (node (ref "C58") (pin "1") (pinfunction "1_1") (pintype "passive"))
      (node (ref "C59") (pin "1") (pinfunction "1_1") (pintype "passive"))
      (node (ref "C6") (pin "2") (pinfunction "2_2") (pintype "passive"))
      (node (ref "C60") (pin "1") (pinfunction "1_1") (pintype "passive"))
      (node (ref "C61") (pin "1") (pinfunction "1_1") (pintype "passive"))
      (node (ref "C62") (pin "2") (pinfunction "2_2") (pintype "passive"))
      (node (ref "C63") (pin "2") (pinfunction "2_2") (pintype "passive"))
      (node (ref "C64") (pin "2") (pinfunction "2_2") (pintype "passive"))
      (node (ref "C65") (pin "2") (pinfunction "2_2") (pintype "passive"))
      (node (ref "C7") (pin "2") (pinfunction "2_2") (pintype "passive"))
      (node (ref "C70") (pin "1") (pinfunction "1_1") (pintype "passive"))
      (node (ref "C72") (pin "1") (pinfunction "1_1") (pintype "passive"))
      (node (ref "C73") (pin "1") (pinfunction "1_1") (pintype "passive"))
      (node (ref "C74") (pin "1") (pinfunction "1_1") (pintype "passive"))
      (node (ref "C75") (pin "1") (pinfunction "1_1") (pintype "passive"))
      (node (ref "C76") (pin "1") (pinfunction "1_1") (pintype "passive"))
      (node (ref "C77") (pin "1") (pinfunction "1_1") (pintype "passive"))
      (node (ref "C78") (pin "1") (pinfunction "1_1") (pintype "passive"))
      (node (ref "C79") (pin "1") (pinfunction "1_1") (pintype "passive"))
      (node (ref "C8") (pin "2") (pinfunction "2_2") (pintype "passive"))
      (node (ref "C9") (pin "2") (pinfunction "2_2") (pintype "passive"))
      (node (ref "JP4") (pin "1") (pinfunction "1_1") (pintype "passive"))
      (node (ref "JP4") (pin "2") (pinfunction "2_2") (pintype "passive"))
      (node (ref "JP4") (pin "3") (pinfunction "3_3") (pintype "passive"))
      (node (ref "JP4") (pin "4") (pinfunction "4_4") (pintype "passive"))
      (node (ref "JP6") (pin "3") (pinfunction "3_3") (pintype "passive"))
      (node (ref "MIC_L") (pin "2") (pinfunction "1_2") (pintype "passive"))
      (node (ref "MIC_R") (pin "2") (pinfunction "1_2") (pintype "passive"))
      (node (ref "Q1") (pin "1") (pinfunction "S_1") (pintype "passive"))
      (node (ref "R1") (pin "1") (pinfunction "1_1") (pintype "passive"))
      (node (ref "R2") (pin "2") (pinfunction "2_2") (pintype "passive"))
      (node (ref "R25") (pin "1") (pinfunction "1_1") (pintype "passive"))
      (node (ref "R28") (pin "2") (pinfunction "2_2") (pintype "passive"))
      (node (ref "U$1") (pin "P$1") (pinfunction "GND_1_P$1") (pintype "bidirectional"))
      (node (ref "U$1") (pin "P$22") (pinfunction "GND_2_P$22") (pintype "bidirectional"))
      (node (ref "U$1") (pin "P$32") (pinfunction "GND_3_P$32") (pintype "bidirectional"))
      (node (ref "U$1") (pin "P$50") (pinfunction "GND_4_P$50") (pintype "bidirectional"))
      (node (ref "U$1") (pin "P$52") (pinfunction "GND_5_P$52") (pintype "bidirectional"))
      (node (ref "U1") (pin "20") (pinfunction "AGND_20") (pintype "power_in"))
      (node (ref "U1") (pin "25") (pinfunction "PGND_25") (pintype "power_in"))
      (node (ref "U1") (pin "26") (pinfunction "PGND-1_26") (pintype "power_in"))
      (node (ref "U1") (pin "31") (pinfunction "PGND-2_31") (pintype "power_in"))
      (node (ref "U1") (pin "32") (pinfunction "PGND-3_32") (pintype "power_in"))
      (node (ref "U1") (pin "33") (pinfunction "POWERPAD_33") (pintype "bidirectional"))
      (node (ref "U1") (pin "5") (pinfunction "DGND_5") (pintype "power_in"))
      (node (ref "U1") (pin "8") (pinfunction "ADR_8") (pintype "input"))
      (node (ref "U2") (pin "20") (pinfunction "AGND_20") (pintype "power_in"))
      (node (ref "U2") (pin "25") (pinfunction "PGND_25") (pintype "power_in"))
      (node (ref "U2") (pin "26") (pinfunction "PGND-1_26") (pintype "power_in"))
      (node (ref "U2") (pin "31") (pinfunction "PGND-2_31") (pintype "power_in"))
      (node (ref "U2") (pin "32") (pinfunction "PGND-3_32") (pintype "power_in"))
      (node (ref "U2") (pin "33") (pinfunction "POWERPAD_33") (pintype "bidirectional"))
      (node (ref "U2") (pin "5") (pinfunction "DGND_5") (pintype "power_in"))
      (node (ref "U4") (pin "11") (pinfunction "GND_11") (pintype "power_in"))
      (node (ref "U4") (pin "5") (pinfunction "ILIM_5") (pintype "passive"))
      (node (ref "U4") (pin "8") (pinfunction "GND_2_8") (pintype "power_in"))
    )
    (net (code "24") (name "Net-(C54-Pad2)") (class "Default")
      (node (ref "C54") (pin "2") (pinfunction "2_2") (pintype "passive"))
      (node (ref "R11") (pin "2") (pinfunction "2_2") (pintype "passive"))
    )
    (net (code "25") (name "Net-(C55-Pad2)") (class "Default")
      (node (ref "C55") (pin "2") (pinfunction "2_2") (pintype "passive"))
      (node (ref "R12") (pin "2") (pinfunction "2_2") (pintype "passive"))
    )
    (net (code "26") (name "Net-(C56-Pad2)") (class "Default")
      (node (ref "C56") (pin "2") (pinfunction "2_2") (pintype "passive"))
      (node (ref "R13") (pin "2") (pinfunction "2_2") (pintype "passive"))
    )
    (net (code "27") (name "Net-(C57-Pad2)") (class "Default")
      (node (ref "C57") (pin "2") (pinfunction "2_2") (pintype "passive"))
      (node (ref "R14") (pin "2") (pinfunction "2_2") (pintype "passive"))
    )
    (net (code "28") (name "Net-(C58-Pad2)") (class "Default")
      (node (ref "C58") (pin "2") (pinfunction "2_2") (pintype "passive"))
      (node (ref "R15") (pin "2") (pinfunction "2_2") (pintype "passive"))
    )
    (net (code "29") (name "Net-(C59-Pad2)") (class "Default")
      (node (ref "C59") (pin "2") (pinfunction "2_2") (pintype "passive"))
      (node (ref "R16") (pin "2") (pinfunction "2_2") (pintype "passive"))
    )
    (net (code "30") (name "Net-(C60-Pad2)") (class "Default")
      (node (ref "C60") (pin "2") (pinfunction "2_2") (pintype "passive"))
      (node (ref "R17") (pin "2") (pinfunction "2_2") (pintype "passive"))
    )
    (net (code "31") (name "Net-(C61-Pad2)") (class "Default")
      (node (ref "C61") (pin "2") (pinfunction "2_2") (pintype "passive"))
      (node (ref "R18") (pin "2") (pinfunction "2_2") (pintype "passive"))
    )
    (net (code "32") (name "Net-(C64-Pad1)") (class "Default")
      (node (ref "C64") (pin "1") (pinfunction "1_1") (pintype "passive"))
      (node (ref "C66") (pin "1") (pinfunction "1_1") (pintype "passive"))
      (node (ref "L9") (pin "2") (pinfunction "2_2") (pintype "passive"))
      (node (ref "R19") (pin "1") (pinfunction "1_1") (pintype "passive"))
    )
    (net (code "33") (name "Net-(C65-Pad1)") (class "Default")
      (node (ref "C65") (pin "1") (pinfunction "1_1") (pintype "passive"))
      (node (ref "C67") (pin "1") (pinfunction "1_1") (pintype "passive"))
      (node (ref "L10") (pin "2") (pinfunction "2_2") (pintype "passive"))
      (node (ref "R20") (pin "1") (pinfunction "1_1") (pintype "passive"))
    )
    (net (code "34") (name "Net-(C66-Pad2)") (class "Default")
      (node (ref "C66") (pin "2") (pinfunction "2_2") (pintype "passive"))
      (node (ref "R22") (pin "2") (pinfunction "2_2") (pintype "passive"))
    )
    (net (code "35") (name "Net-(C67-Pad2)") (class "Default")
      (node (ref "C67") (pin "2") (pinfunction "2_2") (pintype "passive"))
      (node (ref "R24") (pin "2") (pinfunction "2_2") (pintype "passive"))
    )
    (net (code "36") (name "Net-(C68-Pad2)") (class "Default")
      (node (ref "C68") (pin "2") (pinfunction "2_2") (pintype "passive"))
      (node (ref "R21") (pin "2") (pinfunction "2_2") (pintype "passive"))
    )
    (net (code "37") (name "Net-(C69-Pad2)") (class "Default")
      (node (ref "C69") (pin "2") (pinfunction "2_2") (pintype "passive"))
      (node (ref "R23") (pin "2") (pinfunction "2_2") (pintype "passive"))
    )
    (net (code "38") (name "Net-(C72-Pad2)") (class "Default")
      (node (ref "C72") (pin "2") (pinfunction "2_2") (pintype "passive"))
      (node (ref "J2") (pin "2") (pinfunction "2_2") (pintype "bidirectional"))
      (node (ref "L4") (pin "2") (pinfunction "2_2") (pintype "passive"))
      (node (ref "R14") (pin "1") (pinfunction "1_1") (pintype "passive"))
    )
    (net (code "39") (name "Net-(C73-Pad2)") (class "Default")
      (node (ref "C73") (pin "2") (pinfunction "2_2") (pintype "passive"))
      (node (ref "J2") (pin "1") (pinfunction "1_1") (pintype "bidirectional"))
      (node (ref "L3") (pin "2") (pinfunction "2_2") (pintype "passive"))
      (node (ref "R13") (pin "1") (pinfunction "1_1") (pintype "passive"))
    )
    (net (code "40") (name "Net-(C74-Pad2)") (class "Default")
      (node (ref "C74") (pin "2") (pinfunction "2_2") (pintype "passive"))
      (node (ref "J1") (pin "1") (pinfunction "1_1") (pintype "bidirectional"))
      (node (ref "L2") (pin "2") (pinfunction "2_2") (pintype "passive"))
      (node (ref "R12") (pin "1") (pinfunction "1_1") (pintype "passive"))
    )
    (net (code "41") (name "Net-(C75-Pad2)") (class "Default")
      (node (ref "C75") (pin "2") (pinfunction "2_2") (pintype "passive"))
      (node (ref "J1") (pin "2") (pinfunction "2_2") (pintype "bidirectional"))
      (node (ref "L1") (pin "2") (pinfunction "2_2") (pintype "passive"))
      (node (ref "R11") (pin "1") (pinfunction "1_1") (pintype "passive"))
    )
    (net (code "42") (name "Net-(C76-Pad2)") (class "Default")
      (node (ref "C76") (pin "2") (pinfunction "2_2") (pintype "passive"))
      (node (ref "J4") (pin "2") (pinfunction "2_2") (pintype "bidirectional"))
      (node (ref "L8") (pin "2") (pinfunction "2_2") (pintype "passive"))
      (node (ref "R18") (pin "1") (pinfunction "1_1") (pintype "passive"))
    )
    (net (code "43") (name "Net-(C77-Pad2)") (class "Default")
      (node (ref "C77") (pin "2") (pinfunction "2_2") (pintype "passive"))
      (node (ref "J4") (pin "1") (pinfunction "1_1") (pintype "bidirectional"))
      (node (ref "L7") (pin "2") (pinfunction "2_2") (pintype "passive"))
      (node (ref "R17") (pin "1") (pinfunction "1_1") (pintype "passive"))
    )
    (net (code "44") (name "Net-(C78-Pad2)") (class "Default")
      (node (ref "C78") (pin "2") (pinfunction "2_2") (pintype "passive"))
      (node (ref "J3") (pin "1") (pinfunction "1_1") (pintype "bidirectional"))
      (node (ref "L6") (pin "2") (pinfunction "2_2") (pintype "passive"))
      (node (ref "R16") (pin "1") (pinfunction "1_1") (pintype "passive"))
    )
    (net (code "45") (name "Net-(C79-Pad2)") (class "Default")
      (node (ref "C79") (pin "2") (pinfunction "2_2") (pintype "passive"))
      (node (ref "J3") (pin "2") (pinfunction "2_2") (pintype "bidirectional"))
      (node (ref "L5") (pin "2") (pinfunction "2_2") (pintype "passive"))
      (node (ref "R15") (pin "1") (pinfunction "1_1") (pintype "passive"))
    )
    (net (code "46") (name "Net-(MIC_L-2)") (class "Default")
      (node (ref "L9") (pin "1") (pinfunction "1_1") (pintype "passive"))
      (node (ref "MIC_L") (pin "1") (pinfunction "2_1") (pintype "passive"))
    )
    (net (code "47") (name "Net-(MIC_R-2)") (class "Default")
      (node (ref "L10") (pin "1") (pinfunction "1_1") (pintype "passive"))
      (node (ref "MIC_R") (pin "1") (pinfunction "2_1") (pintype "passive"))
    )
    (net (code "48") (name "Net-(Q1-G)") (class "Default")
      (node (ref "C71") (pin "2") (pinfunction "2_2") (pintype "passive"))
      (node (ref "Q1") (pin "2") (pinfunction "G_2") (pintype "passive"))
      (node (ref "R28") (pin "1") (pinfunction "1_1") (pintype "passive"))
    )
    (net (code "49") (name "Net-(TP1-1)") (class "Default")
      (node (ref "R3") (pin "1") (pinfunction "1_1") (pintype "passive"))
      (node (ref "TP1") (pin "P$1") (pinfunction "1_P$1") (pintype "bidirectional"))
      (node (ref "U1") (pin "10") (pinfunction "GPIO1_10") (pintype "bidirectional"))
    )
    (net (code "50") (name "Net-(TP3-1)") (class "Default")
      (node (ref "R4") (pin "1") (pinfunction "1_1") (pintype "passive"))
      (node (ref "TP3") (pin "P$1") (pinfunction "1_P$1") (pintype "bidirectional"))
      (node (ref "U1") (pin "9") (pinfunction "GPIOO_9") (pintype "bidirectional"))
    )
    (net (code "51") (name "Net-(TP4-1)") (class "Default")
      (node (ref "R6") (pin "1") (pinfunction "1_1") (pintype "passive"))
      (node (ref "TP4") (pin "P$1") (pinfunction "1_P$1") (pintype "bidirectional"))
      (node (ref "U2") (pin "10") (pinfunction "GPIO1_10") (pintype "bidirectional"))
    )
    (net (code "52") (name "Net-(TP5-1)") (class "Default")
      (node (ref "TP5") (pin "P$1") (pinfunction "1_P$1") (pintype "bidirectional"))
      (node (ref "U2") (pin "11") (pinfunction "GPIO2_11") (pintype "bidirectional"))
    )
    (net (code "53") (name "Net-(TP6-1)") (class "Default")
      (node (ref "R7") (pin "1") (pinfunction "1_1") (pintype "passive"))
      (node (ref "TP6") (pin "P$1") (pinfunction "1_P$1") (pintype "bidirectional"))
      (node (ref "U2") (pin "9") (pinfunction "GPIOO_9") (pintype "bidirectional"))
    )
    (net (code "54") (name "Net-(TP7-1)") (class "Default")
      (node (ref "C70") (pin "2") (pinfunction "2_2") (pintype "passive"))
      (node (ref "R26") (pin "2") (pinfunction "2_2") (pintype "passive"))
      (node (ref "TP7") (pin "P$1") (pinfunction "1_P$1") (pintype "bidirectional"))
      (node (ref "U$1") (pin "P$8") (pinfunction "RESET_P$8") (pintype "bidirectional"))
    )
    (net (code "55") (name "Net-(U1-AVDD)") (class "Default")
      (node (ref "C23") (pin "1") (pinfunction "1_1") (pintype "passive"))
      (node (ref "U1") (pin "19") (pinfunction "AVDD_19") (pintype "power_in"))
    )
    (net (code "56") (name "Net-(U1-BST_A+)") (class "Default")
      (node (ref "C27") (pin "1") (pinfunction "1_1") (pintype "passive"))
      (node (ref "U1") (pin "1") (pinfunction "BST_A+_1") (pintype "power_in"))
    )
    (net (code "57") (name "Net-(U1-BST_A-)") (class "Default")
      (node (ref "C28") (pin "1") (pinfunction "1_1") (pintype "passive"))
      (node (ref "U1") (pin "29") (pinfunction "BST_A-_29") (pintype "power_in"))
    )
    (net (code "58") (name "Net-(U1-BST_B+)") (class "Default")
      (node (ref "C29") (pin "1") (pinfunction "1_1") (pintype "passive"))
      (node (ref "U1") (pin "24") (pinfunction "BST_B+_24") (pintype "power_in"))
    )
    (net (code "59") (name "Net-(U1-BST_B-)") (class "Default")
      (node (ref "C30") (pin "1") (pinfunction "1_1") (pintype "passive"))
      (node (ref "U1") (pin "28") (pinfunction "BST_B-_28") (pintype "power_in"))
    )
    (net (code "60") (name "Net-(U1-GVDD)") (class "Default")
      (node (ref "C26") (pin "1") (pinfunction "1_1") (pintype "passive"))
      (node (ref "U1") (pin "18") (pinfunction "GVDD_18") (pintype "power_in"))
    )
    (net (code "61") (name "Net-(U1-OUT_A+)") (class "Default")
      (node (ref "C27") (pin "2") (pinfunction "2_2") (pintype "passive"))
      (node (ref "L1") (pin "1") (pinfunction "1_1") (pintype "passive"))
      (node (ref "U1") (pin "2") (pinfunction "OUT_A+_2") (pintype "output"))
    )
    (net (code "62") (name "Net-(U1-OUT_A-)") (class "Default")
      (node (ref "C28") (pin "2") (pinfunction "2_2") (pintype "passive"))
      (node (ref "L2") (pin "1") (pinfunction "1_1") (pintype "passive"))
      (node (ref "U1") (pin "30") (pinfunction "OUT_A-_30") (pintype "output"))
    )
    (net (code "63") (name "Net-(U1-OUT_B+)") (class "Default")
      (node (ref "C29") (pin "2") (pinfunction "2_2") (pintype "passive"))
      (node (ref "L3") (pin "1") (pinfunction "1_1") (pintype "passive"))
      (node (ref "U1") (pin "23") (pinfunction "OUT_B+_23") (pintype "output"))
    )
    (net (code "64") (name "Net-(U1-OUT_B-)") (class "Default")
      (node (ref "C30") (pin "2") (pinfunction "2_2") (pintype "passive"))
      (node (ref "L4") (pin "1") (pinfunction "1_1") (pintype "passive"))
      (node (ref "U1") (pin "27") (pinfunction "OUT_B-_27") (pintype "output"))
    )
    (net (code "65") (name "Net-(U1-VR_DIG)") (class "Default")
      (node (ref "C21") (pin "1") (pinfunction "1_1") (pintype "passive"))
      (node (ref "U1") (pin "7") (pinfunction "VR_DIG_7") (pintype "power_in"))
    )
    (net (code "66") (name "Net-(U2-ADR)") (class "Default")
      (node (ref "R1") (pin "2") (pinfunction "2_2") (pintype "passive"))
      (node (ref "U2") (pin "8") (pinfunction "ADR_8") (pintype "input"))
    )
    (net (code "67") (name "Net-(U2-AVDD)") (class "Default")
      (node (ref "C24") (pin "1") (pinfunction "1_1") (pintype "passive"))
      (node (ref "U2") (pin "19") (pinfunction "AVDD_19") (pintype "power_in"))
    )
    (net (code "68") (name "Net-(U2-BST_A+)") (class "Default")
      (node (ref "C31") (pin "1") (pinfunction "1_1") (pintype "passive"))
      (node (ref "U2") (pin "1") (pinfunction "BST_A+_1") (pintype "power_in"))
    )
    (net (code "69") (name "Net-(U2-BST_A-)") (class "Default")
      (node (ref "C32") (pin "1") (pinfunction "1_1") (pintype "passive"))
      (node (ref "U2") (pin "29") (pinfunction "BST_A-_29") (pintype "power_in"))
    )
    (net (code "70") (name "Net-(U2-BST_B+)") (class "Default")
      (node (ref "C33") (pin "1") (pinfunction "1_1") (pintype "passive"))
      (node (ref "U2") (pin "24") (pinfunction "BST_B+_24") (pintype "power_in"))
    )
    (net (code "71") (name "Net-(U2-BST_B-)") (class "Default")
      (node (ref "C34") (pin "1") (pinfunction "1_1") (pintype "passive"))
      (node (ref "U2") (pin "28") (pinfunction "BST_B-_28") (pintype "power_in"))
    )
    (net (code "72") (name "Net-(U2-GVDD)") (class "Default")
      (node (ref "C25") (pin "1") (pinfunction "1_1") (pintype "passive"))
      (node (ref "U2") (pin "18") (pinfunction "GVDD_18") (pintype "power_in"))
    )
    (net (code "73") (name "Net-(U2-OUT_A+)") (class "Default")
      (node (ref "C31") (pin "2") (pinfunction "2_2") (pintype "passive"))
      (node (ref "L5") (pin "1") (pinfunction "1_1") (pintype "passive"))
      (node (ref "U2") (pin "2") (pinfunction "OUT_A+_2") (pintype "output"))
    )
    (net (code "74") (name "Net-(U2-OUT_A-)") (class "Default")
      (node (ref "C32") (pin "2") (pinfunction "2_2") (pintype "passive"))
      (node (ref "L6") (pin "1") (pinfunction "1_1") (pintype "passive"))
      (node (ref "U2") (pin "30") (pinfunction "OUT_A-_30") (pintype "output"))
    )
    (net (code "75") (name "Net-(U2-OUT_B+)") (class "Default")
      (node (ref "C33") (pin "2") (pinfunction "2_2") (pintype "passive"))
      (node (ref "L7") (pin "1") (pinfunction "1_1") (pintype "passive"))
      (node (ref "U2") (pin "23") (pinfunction "OUT_B+_23") (pintype "output"))
    )
    (net (code "76") (name "Net-(U2-OUT_B-)") (class "Default")
      (node (ref "C34") (pin "2") (pinfunction "2_2") (pintype "passive"))
      (node (ref "L8") (pin "1") (pinfunction "1_1") (pintype "passive"))
      (node (ref "U2") (pin "27") (pinfunction "OUT_B-_27") (pintype "output"))
    )
    (net (code "77") (name "Net-(U2-VR_DIG)") (class "Default")
      (node (ref "C22") (pin "1") (pinfunction "1_1") (pintype "passive"))
      (node (ref "U2") (pin "7") (pinfunction "VR_DIG_7") (pintype "power_in"))
    )
    (net (code "78") (name "Net-(U4-SET)") (class "Default")
      (node (ref "C43") (pin "1") (pinfunction "1_1") (pintype "passive"))
      (node (ref "R2") (pin "1") (pinfunction "1_1") (pintype "passive"))
      (node (ref "U4") (pin "7") (pinfunction "SET_7") (pintype "input"))
    )
    (net (code "79") (name "VBAT") (class "Default")
      (node (ref "C1") (pin "1") (pinfunction "1_1") (pintype "passive"))
      (node (ref "C10") (pin "1") (pinfunction "1_1") (pintype "passive"))
      (node (ref "C11") (pin "1") (pinfunction "1_1") (pintype "passive"))
      (node (ref "C12") (pin "1") (pinfunction "1_1") (pintype "passive"))
      (node (ref "C13") (pin "1") (pinfunction "1_1") (pintype "passive"))
      (node (ref "C14") (pin "1") (pinfunction "1_1") (pintype "passive"))
      (node (ref "C15") (pin "1") (pinfunction "1_1") (pintype "passive"))
      (node (ref "C16") (pin "1") (pinfunction "1_1") (pintype "passive"))
      (node (ref "C2") (pin "1") (pinfunction "1_1") (pintype "passive"))
      (node (ref "C3") (pin "1") (pinfunction "1_1") (pintype "passive"))
      (node (ref "C35") (pin "2") (pinfunction "2_2") (pintype "passive"))
      (node (ref "C4") (pin "1") (pinfunction "1_1") (pintype "passive"))
      (node (ref "C45") (pin "1") (pinfunction "1_1") (pintype "passive"))
      (node (ref "C46") (pin "1") (pinfunction "1_1") (pintype "passive"))
      (node (ref "C47") (pin "1") (pinfunction "1_1") (pintype "passive"))
      (node (ref "C48") (pin "1") (pinfunction "1_1") (pintype "passive"))
      (node (ref "C49") (pin "1") (pinfunction "1_1") (pintype "passive"))
      (node (ref "C5") (pin "1") (pinfunction "1_1") (pintype "passive"))
      (node (ref "C50") (pin "1") (pinfunction "1_1") (pintype "passive"))
      (node (ref "C51") (pin "1") (pinfunction "1_1") (pintype "passive"))
      (node (ref "C52") (pin "1") (pinfunction "1_1") (pintype "passive"))
      (node (ref "C6") (pin "1") (pinfunction "1_1") (pintype "passive"))
      (node (ref "C7") (pin "1") (pinfunction "1_1") (pintype "passive"))
      (node (ref "C8") (pin "1") (pinfunction "1_1") (pintype "passive"))
      (node (ref "C9") (pin "1") (pinfunction "1_1") (pintype "passive"))
      (node (ref "JP3") (pin "1") (pinfunction "1_1") (pintype "passive"))
      (node (ref "JP3") (pin "2") (pinfunction "2_2") (pintype "passive"))
      (node (ref "JP3") (pin "3") (pinfunction "3_3") (pintype "passive"))
      (node (ref "JP3") (pin "4") (pinfunction "4_4") (pintype "passive"))
      (node (ref "JP6") (pin "4") (pinfunction "4_4") (pintype "passive"))
      (node (ref "U1") (pin "21") (pinfunction "PVDD-3_21") (pintype "power_in"))
      (node (ref "U1") (pin "22") (pinfunction "PVDD-2_22") (pintype "power_in"))
      (node (ref "U1") (pin "3") (pinfunction "PVDD-1_3") (pintype "power_in"))
      (node (ref "U1") (pin "4") (pinfunction "PVDD_4") (pintype "power_in"))
      (node (ref "U2") (pin "21") (pinfunction "PVDD-3_21") (pintype "power_in"))
      (node (ref "U2") (pin "22") (pinfunction "PVDD-2_22") (pintype "power_in"))
      (node (ref "U2") (pin "3") (pinfunction "PVDD-1_3") (pintype "power_in"))
      (node (ref "U2") (pin "4") (pinfunction "PVDD_4") (pintype "power_in"))
      (node (ref "U4") (pin "1") (pinfunction "IN_2_1") (pintype "input"))
      (node (ref "U4") (pin "2") (pinfunction "IN_2") (pintype "input"))
      (node (ref "U4") (pin "6") (pinfunction "PGFB_6") (pintype "power_in"))
    )
    (net (code "80") (name "unconnected-(MP1-P$1-Pad1)") (class "Default")
      (node (ref "MP1") (pin "1") (pinfunction "P$1_1") (pintype "passive"))
    )
    (net (code "81") (name "unconnected-(MP2-P$1-Pad1)") (class "Default")
      (node (ref "MP2") (pin "1") (pinfunction "P$1_1") (pintype "passive"))
    )
    (net (code "82") (name "unconnected-(U$1-1.8V_OUT-PadP$35)") (class "Default")
      (node (ref "U$1") (pin "P$35") (pinfunction "1.8V_OUT_P$35") (pintype "bidirectional"))
    )
    (net (code "83") (name "unconnected-(U$1-AIO0-PadP$2)") (class "Default")
      (node (ref "U$1") (pin "P$2") (pinfunction "AIO0_P$2") (pintype "bidirectional"))
    )
    (net (code "84") (name "unconnected-(U$1-AIO1-PadP$3)") (class "Default")
      (node (ref "U$1") (pin "P$3") (pinfunction "AIO1_P$3") (pintype "bidirectional"))
    )
    (net (code "85") (name "unconnected-(U$1-BT_CTS-PadP$15)") (class "Default")
      (node (ref "U$1") (pin "P$15") (pinfunction "BT_CTS_P$15") (pintype "bidirectional"))
    )
    (net (code "86") (name "unconnected-(U$1-BT_RTS-PadP$16)") (class "Default")
      (node (ref "U$1") (pin "P$16") (pinfunction "BT_RTS_P$16") (pintype "bidirectional"))
    )
    (net (code "87") (name "unconnected-(U$1-EXT_ANT-PadP$51)") (class "Default")
      (node (ref "U$1") (pin "P$51") (pinfunction "EXT_ANT_P$51") (pintype "bidirectional"))
    )
    (net (code "88") (name "unconnected-(U$1-I2S_IN-PadP$5)") (class "Default")
      (node (ref "U$1") (pin "P$5") (pinfunction "I2S_IN_P$5") (pintype "bidirectional"))
    )
    (net (code "89") (name "unconnected-(U$1-LED1-PadP$18)") (class "Default")
      (node (ref "U$1") (pin "P$18") (pinfunction "LED1_P$18") (pintype "bidirectional"))
    )
    (net (code "90") (name "unconnected-(U$1-LED2-PadP$19)") (class "Default")
      (node (ref "U$1") (pin "P$19") (pinfunction "LED2_P$19") (pintype "bidirectional"))
    )
    (net (code "91") (name "unconnected-(U$1-PIO0-PadP$20)") (class "Default")
      (node (ref "U$1") (pin "P$20") (pinfunction "PIO0_P$20") (pintype "bidirectional"))
    )
    (net (code "92") (name "unconnected-(U$1-PIO1-PadP$21)") (class "Default")
      (node (ref "U$1") (pin "P$21") (pinfunction "PIO1_P$21") (pintype "bidirectional"))
    )
    (net (code "93") (name "unconnected-(U$1-PIO2-PadP$23)") (class "Default")
      (node (ref "U$1") (pin "P$23") (pinfunction "PIO2_P$23") (pintype "bidirectional"))
    )
    (net (code "94") (name "unconnected-(U$1-PIO3-PadP$24)") (class "Default")
      (node (ref "U$1") (pin "P$24") (pinfunction "PIO3_P$24") (pintype "bidirectional"))
    )
    (net (code "95") (name "unconnected-(U$1-PIO4-PadP$25)") (class "Default")
      (node (ref "U$1") (pin "P$25") (pinfunction "PIO4_P$25") (pintype "bidirectional"))
    )
    (net (code "96") (name "unconnected-(U$1-PIO5-PadP$26)") (class "Default")
      (node (ref "U$1") (pin "P$26") (pinfunction "PIO5_P$26") (pintype "bidirectional"))
    )
    (net (code "97") (name "unconnected-(U$1-PIO14-PadP$29)") (class "Default")
      (node (ref "U$1") (pin "P$29") (pinfunction "PIO14_P$29") (pintype "bidirectional"))
    )
    (net (code "98") (name "unconnected-(U$1-PIO15-PadP$30)") (class "Default")
      (node (ref "U$1") (pin "P$30") (pinfunction "PIO15_P$30") (pintype "bidirectional"))
    )
    (net (code "99") (name "unconnected-(U$1-SPI_CLK-PadP$12)") (class "Default")
      (node (ref "U$1") (pin "P$12") (pinfunction "SPI_CLK_P$12") (pintype "bidirectional"))
    )
    (net (code "100") (name "unconnected-(U$1-SPI_CSB-PadP$9)") (class "Default")
      (node (ref "U$1") (pin "P$9") (pinfunction "SPI_CSB_P$9") (pintype "bidirectional"))
    )
    (net (code "101") (name "unconnected-(U$1-SPI_MISO-PadP$11)") (class "Default")
      (node (ref "U$1") (pin "P$11") (pinfunction "SPI_MISO_P$11") (pintype "bidirectional"))
    )
    (net (code "102") (name "unconnected-(U$1-SPI_MOSI-PadP$10)") (class "Default")
      (node (ref "U$1") (pin "P$10") (pinfunction "SPI_MOSI_P$10") (pintype "bidirectional"))
    )
    (net (code "103") (name "unconnected-(U$1-SPK_LN-PadP$48)") (class "Default")
      (node (ref "U$1") (pin "P$48") (pinfunction "SPK_LN_P$48") (pintype "bidirectional"))
    )
    (net (code "104") (name "unconnected-(U$1-SPK_LP-PadP$49)") (class "Default")
      (node (ref "U$1") (pin "P$49") (pinfunction "SPK_LP_P$49") (pintype "bidirectional"))
    )
    (net (code "105") (name "unconnected-(U$1-SPK_RN-PadP$46)") (class "Default")
      (node (ref "U$1") (pin "P$46") (pinfunction "SPK_RN_P$46") (pintype "bidirectional"))
    )
    (net (code "106") (name "unconnected-(U$1-SPK_RP-PadP$47)") (class "Default")
      (node (ref "U$1") (pin "P$47") (pinfunction "SPK_RP_P$47") (pintype "bidirectional"))
    )
    (net (code "107") (name "unconnected-(U$1-USB_DN-PadP$38)") (class "Default")
      (node (ref "U$1") (pin "P$38") (pinfunction "USB_DN_P$38") (pintype "bidirectional"))
    )
    (net (code "108") (name "unconnected-(U$1-USB_DP-PadP$37)") (class "Default")
      (node (ref "U$1") (pin "P$37") (pinfunction "USB_DP_P$37") (pintype "bidirectional"))
    )
    (net (code "109") (name "unconnected-(U$1-VCC_CHG-PadP$39)") (class "Default")
      (node (ref "U$1") (pin "P$39") (pinfunction "VCC_CHG_P$39") (pintype "bidirectional"))
    )
    (net (code "110") (name "unconnected-(U$1-VDD_USB{slash}3.3VO-PadP$31)") (class "Default")
      (node (ref "U$1") (pin "P$31") (pinfunction "VDD_USB/3.3VO_P$31") (pintype "bidirectional"))
    )
  )
)
